# airquality-schematic.net
KiCad netlist of a schematic drawn in EAGLE
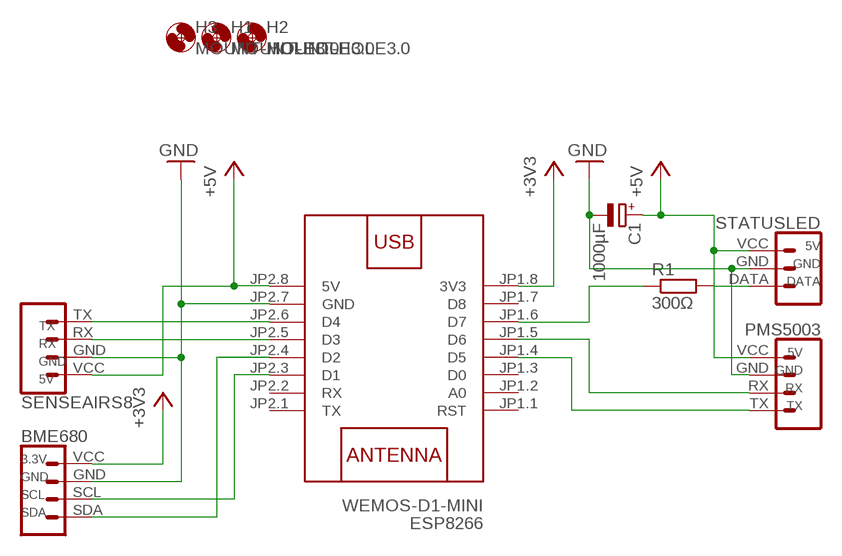
[diagram p0: schematic, sheet 1]

(export (version "E")
  (design (tool "Eeschema 10.0.6"))
  (components
    (comp (ref "BME680")
      (value "BME680")
      (footprint "eagle-import:BME680")
      (libsource (lib "eagle-import") (part "BME680"))
    )
    (comp (ref "C1")
      (value "1000µF")
      (footprint "eagle-import:E5-10,5")
      (libsource (lib "eagle-import") (part "CPOL-EUE5-10.5"))
    )
    (comp (ref "ESP8266")
      (value "WEMOS-D1-MINI")
      (footprint "eagle-import:WEMOS-D1-MINI")
      (libsource (lib "eagle-import") (part "WEMOS-D1-MINI"))
    )
    (comp (ref "H1")
      (value "MOUNT-HOLE3.0")
      (footprint "eagle-import:3,0")
      (libsource (lib "eagle-import") (part "MOUNT-HOLE3.0"))
    )
    (comp (ref "H2")
      (value "MOUNT-HOLE3.0")
      (footprint "eagle-import:3,0")
      (libsource (lib "eagle-import") (part "MOUNT-HOLE3.0"))
    )
    (comp (ref "H3")
      (value "MOUNT-HOLE3.0")
      (footprint "eagle-import:3,0")
      (libsource (lib "eagle-import") (part "MOUNT-HOLE3.0"))
    )
    (comp (ref "PMS5003")
      (value "PMS5003")
      (footprint "eagle-import:PMS5003")
      (libsource (lib "eagle-import") (part "PMS5003"))
    )
    (comp (ref "R1")
      (value "300Ω")
      (footprint "eagle-import:0207_10")
      (libsource (lib "eagle-import") (part "R-EU_0207/10"))
    )
    (comp (ref "SENSEAIRS8")
      (value "SENSEAIRS8")
      (footprint "eagle-import:SENSEAIRS8")
      (libsource (lib "eagle-import") (part "SENSEAIRS8"))
    )
    (comp (ref "STATUSLED")
      (value "LED")
      (footprint "eagle-import:LED")
      (libsource (lib "eagle-import") (part "LED"))
    )
  )
  (nets
    (net (code "1") (name "+3V3") (class "Default")
      (node (ref "BME680") (pin "VCC") (pinfunction "VCC_VCC") (pintype "passive"))
      (node (ref "ESP8266") (pin "JP1.8") (pinfunction "3V3_JP1.8") (pintype "power_in"))
    )
    (net (code "2") (name "+5V") (class "Default")
      (node (ref "C1") (pin "+") (pinfunction "+_+") (pintype "passive"))
      (node (ref "ESP8266") (pin "JP2.8") (pinfunction "5V_JP2.8") (pintype "power_in"))
      (node (ref "PMS5003") (pin "VCC") (pinfunction "VCC_VCC") (pintype "passive"))
      (node (ref "SENSEAIRS8") (pin "VCC") (pinfunction "VCC_VCC") (pintype "passive"))
      (node (ref "STATUSLED") (pin "VCC") (pinfunction "VCC_VCC") (pintype "passive"))
    )
    (net (code "3") (name "GND") (class "Default")
      (node (ref "BME680") (pin "GND") (pinfunction "GND_GND") (pintype "passive"))
      (node (ref "C1") (pin "-") (pinfunction "-_-") (pintype "passive"))
      (node (ref "ESP8266") (pin "JP2.7") (pinfunction "GND_JP2.7") (pintype "power_in"))
      (node (ref "PMS5003") (pin "GND") (pinfunction "GND_GND") (pintype "passive"))
      (node (ref "SENSEAIRS8") (pin "GND") (pinfunction "GND_GND") (pintype "passive"))
      (node (ref "STATUSLED") (pin "GND") (pinfunction "GND_GND") (pintype "passive"))
    )
    (net (code "4") (name "Net-(ESP8266-D1)") (class "Default")
      (node (ref "BME680") (pin "SCL") (pinfunction "SCL_SCL") (pintype "passive"))
      (node (ref "ESP8266") (pin "JP2.3") (pinfunction "D1_JP2.3") (pintype "bidirectional"))
    )
    (net (code "5") (name "Net-(ESP8266-D2)") (class "Default")
      (node (ref "BME680") (pin "SDA") (pinfunction "SDA_SDA") (pintype "passive"))
      (node (ref "ESP8266") (pin "JP2.4") (pinfunction "D2_JP2.4") (pintype "bidirectional"))
    )
    (net (code "6") (name "Net-(ESP8266-D3)") (class "Default")
      (node (ref "ESP8266") (pin "JP2.5") (pinfunction "D3_JP2.5") (pintype "bidirectional"))
      (node (ref "SENSEAIRS8") (pin "RX") (pinfunction "RX_RX") (pintype "passive"))
    )
    (net (code "7") (name "Net-(ESP8266-D4)") (class "Default")
      (node (ref "ESP8266") (pin "JP2.6") (pinfunction "D4_JP2.6") (pintype "bidirectional"))
      (node (ref "SENSEAIRS8") (pin "TX") (pinfunction "TX_TX") (pintype "passive"))
    )
    (net (code "8") (name "Net-(ESP8266-D5)") (class "Default")
      (node (ref "ESP8266") (pin "JP1.4") (pinfunction "D5_JP1.4") (pintype "bidirectional"))
      (node (ref "PMS5003") (pin "TX") (pinfunction "TX_TX") (pintype "passive"))
    )
    (net (code "9") (name "Net-(ESP8266-D6)") (class "Default")
      (node (ref "ESP8266") (pin "JP1.5") (pinfunction "D6_JP1.5") (pintype "bidirectional"))
      (node (ref "PMS5003") (pin "RX") (pinfunction "RX_RX") (pintype "passive"))
    )
    (net (code "10") (name "Net-(ESP8266-D7)") (class "Default")
      (node (ref "ESP8266") (pin "JP1.6") (pinfunction "D7_JP1.6") (pintype "bidirectional"))
      (node (ref "R1") (pin "1") (pinfunction "1_1") (pintype "passive"))
    )
    (net (code "11") (name "Net-(R1-Pad2)") (class "Default")
      (node (ref "R1") (pin "2") (pinfunction "2_2") (pintype "passive"))
      (node (ref "STATUSLED") (pin "DATA") (pinfunction "DATA_DATA") (pintype "passive"))
    )
    (net (code "12") (name "unconnected-(ESP8266-A0-PadJP1.2)") (class "Default")
      (node (ref "ESP8266") (pin "JP1.2") (pinfunction "A0_JP1.2") (pintype "bidirectional"))
    )
    (net (code "13") (name "unconnected-(ESP8266-D0-PadJP1.3)") (class "Default")
      (node (ref "ESP8266") (pin "JP1.3") (pinfunction "D0_JP1.3") (pintype "bidirectional"))
    )
    (net (code "14") (name "unconnected-(ESP8266-D8-PadJP1.7)") (class "Default")
      (node (ref "ESP8266") (pin "JP1.7") (pinfunction "D8_JP1.7") (pintype "bidirectional"))
    )
    (net (code "15") (name "unconnected-(ESP8266-RST-PadJP1.1)") (class "Default")
      (node (ref "ESP8266") (pin "JP1.1") (pinfunction "RST_JP1.1") (pintype "bidirectional"))
    )
    (net (code "16") (name "unconnected-(ESP8266-RX-PadJP2.2)") (class "Default")
      (node (ref "ESP8266") (pin "JP2.2") (pinfunction "RX_JP2.2") (pintype "bidirectional"))
    )
    (net (code "17") (name "unconnected-(ESP8266-TX-PadJP2.1)") (class "Default")
      (node (ref "ESP8266") (pin "JP2.1") (pinfunction "TX_JP2.1") (pintype "bidirectional"))
    )
  )
)
